# basestation_lorawan.net
KiCad netlist of a schematic drawn in EAGLE
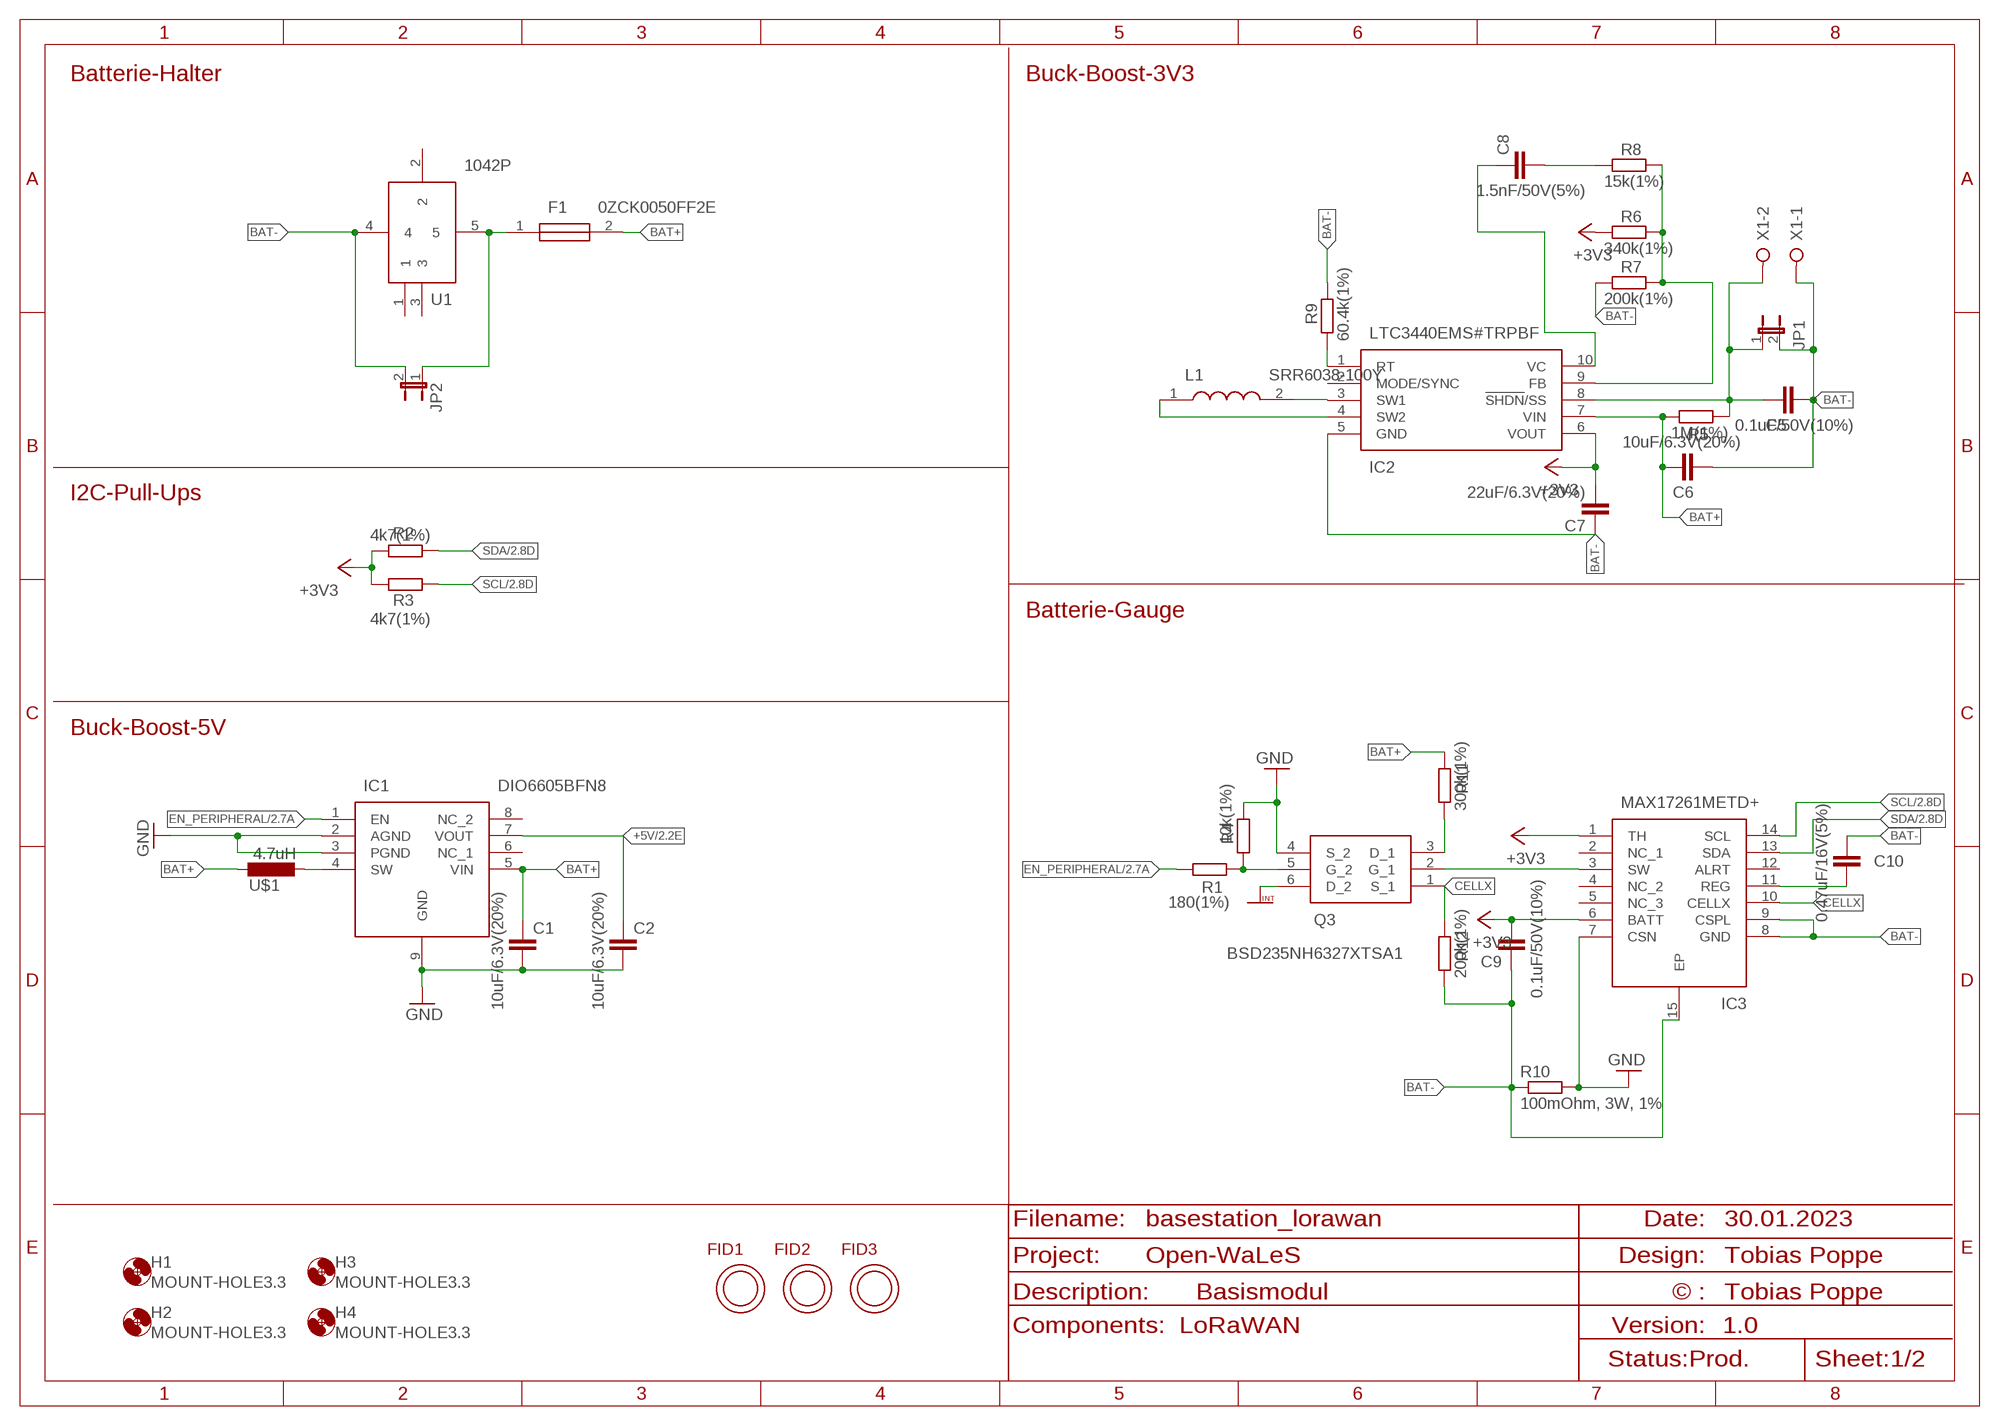
[diagram p0: schematic, sheet 1]
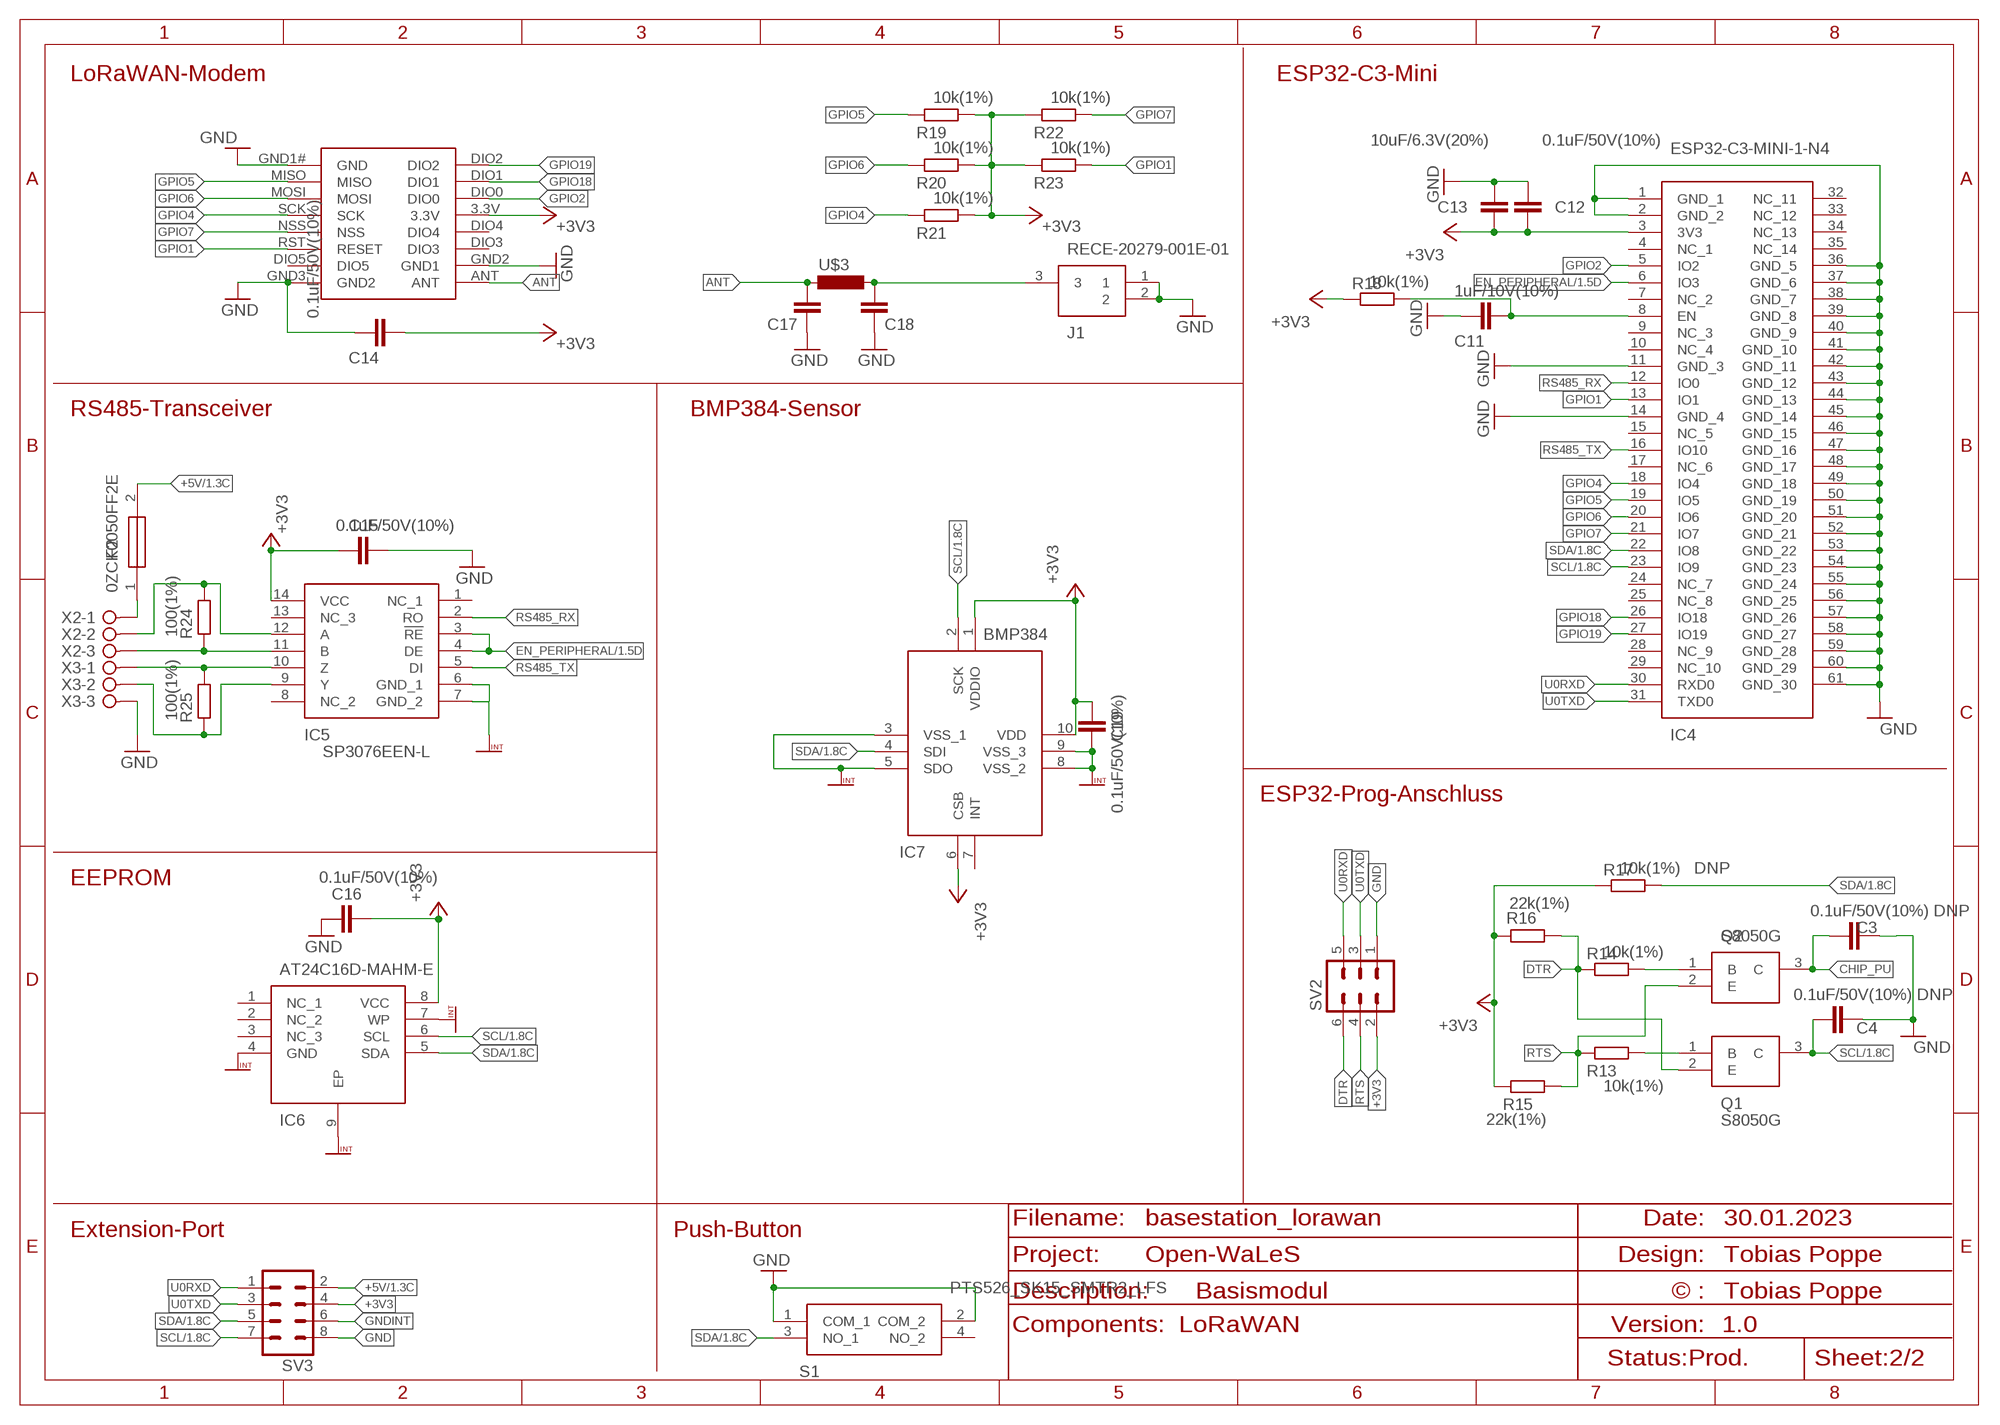
[diagram p1: schematic, sheet 2]

(export (version "E")
  (design (tool "Eeschema 10.0.6"))
  (components
    (comp (ref "C1")
      (value "10uF/6.3V(20%)")
      (footprint "eagle-import:C0805")
      (libsource (lib "eagle-import") (part "C-EUC0805"))
    )
    (comp (ref "C2")
      (value "10uF/6.3V(20%)")
      (footprint "eagle-import:C0805")
      (libsource (lib "eagle-import") (part "C-EUC0805"))
    )
    (comp (ref "C5")
      (value "0.1uF/50V(10%)")
      (footprint "eagle-import:C0805")
      (libsource (lib "eagle-import") (part "C-EUC0805"))
    )
    (comp (ref "C6")
      (value "10uF/6.3V(20%)")
      (footprint "eagle-import:C0805")
      (libsource (lib "eagle-import") (part "C-EUC0805"))
    )
    (comp (ref "C7")
      (value "22uF/6.3V(20%)")
      (footprint "eagle-import:C0805K")
      (libsource (lib "eagle-import") (part "C-EUC0805K"))
    )
    (comp (ref "C8")
      (value "1.5nF/50V(5%)")
      (footprint "eagle-import:C0805")
      (libsource (lib "eagle-import") (part "C-EUC0805"))
    )
    (comp (ref "C9")
      (value "0.1uF/50V(10%)")
      (footprint "eagle-import:C0805")
      (libsource (lib "eagle-import") (part "C-EUC0805"))
    )
    (comp (ref "C10")
      (value "0.47uF/16V(5%)")
      (footprint "eagle-import:C0805")
      (libsource (lib "eagle-import") (part "C-EUC0805"))
    )
    (comp (ref "F1")
      (value "0ZCK0050FF2E")
      (footprint "eagle-import:FUSC2214X125N")
      (libsource (lib "eagle-import") (part "0ZCK0050FF2E"))
    )
    (comp (ref "FID1")
      (value "OPEN-PNP-FIDUCIAL")
      (footprint "eagle-import:OPEN-PNP-FIDUCIAL")
      (libsource (lib "eagle-import") (part "OPEN-PNP-FIDUCIAL"))
    )
    (comp (ref "FID2")
      (value "OPEN-PNP-FIDUCIAL")
      (footprint "eagle-import:OPEN-PNP-FIDUCIAL")
      (libsource (lib "eagle-import") (part "OPEN-PNP-FIDUCIAL"))
    )
    (comp (ref "FID3")
      (value "OPEN-PNP-FIDUCIAL")
      (footprint "eagle-import:OPEN-PNP-FIDUCIAL")
      (libsource (lib "eagle-import") (part "OPEN-PNP-FIDUCIAL"))
    )
    (comp (ref "H1")
      (value "MOUNT-HOLE3.3")
      (footprint "eagle-import:3,3")
      (libsource (lib "eagle-import") (part "MOUNT-HOLE3.3"))
    )
    (comp (ref "H2")
      (value "MOUNT-HOLE3.3")
      (footprint "eagle-import:3,3")
      (libsource (lib "eagle-import") (part "MOUNT-HOLE3.3"))
    )
    (comp (ref "H3")
      (value "MOUNT-HOLE3.3")
      (footprint "eagle-import:3,3")
      (libsource (lib "eagle-import") (part "MOUNT-HOLE3.3"))
    )
    (comp (ref "H4")
      (value "MOUNT-HOLE3.3")
      (footprint "eagle-import:3,3")
      (libsource (lib "eagle-import") (part "MOUNT-HOLE3.3"))
    )
    (comp (ref "IC1")
      (value "DIO6605BFN8")
      (footprint "eagle-import:SON50P300X200X80-9N")
      (fields (field (name "MOUSER_PART_NUMBER") "453-DIO6605BFN8"))
      (libsource (lib "eagle-import") (part "DIO6605BFN8"))
    )
    (comp (ref "IC2")
      (value "LTC3440EMS#TRPBF")
      (footprint "eagle-import:SOP50P490X110-10N")
      (fields (field (name "MOUSER_PART_NUMBER") "584-LTC3440EMS#TRPBF"))
      (libsource (lib "eagle-import") (part "LTC3440EMS#TRPBF"))
    )
    (comp (ref "IC3")
      (value "MAX17261METD+")
      (footprint "eagle-import:SON40P300X300X80-15N")
      (fields (field (name "MOUSER_PART_NUMBER") "700-MAX17261METD+"))
      (libsource (lib "eagle-import") (part "MAX17261METD+"))
    )
    (comp (ref "JP1")
      (value "JP1E")
      (footprint "eagle-import:JP1")
      (libsource (lib "eagle-import") (part "JP1E"))
    )
    (comp (ref "JP2")
      (value "JP1E")
      (footprint "eagle-import:JP1")
      (libsource (lib "eagle-import") (part "JP1E"))
    )
    (comp (ref "L1")
      (value "SRR6038-100Y")
      (footprint "eagle-import:SRR6038330Y")
      (fields
        (field (name "ARROW_PART_NUMBER") "SRR6038-330Y")
        (field (name "MOUSER_PART_NUMBER") "652-SRR6038-330Y")
        (field (name "MOUSER_PART_NUMBER_1") "652-SRR6038-100Y")
      )
      (libsource (lib "eagle-import") (part "SRR6038-330Y"))
    )
    (comp (ref "Q3")
      (value "BSD235NH6327XTSA1")
      (footprint "eagle-import:SOT65P210X100-6N")
      (fields (field (name "MOUSER_PART_NUMBER") "726-BSD235NH6327XTS"))
      (libsource (lib "eagle-import") (part "BSD235NH6327XTSA1"))
    )
    (comp (ref "R1")
      (value "180(1%)")
      (footprint "eagle-import:M0805")
      (libsource (lib "eagle-import") (part "R-EU_M0805"))
    )
    (comp (ref "R2")
      (value "4k7(1%)")
      (footprint "eagle-import:M0805")
      (libsource (lib "eagle-import") (part "R-EU_M0805"))
    )
    (comp (ref "R3")
      (value "4k7(1%)")
      (footprint "eagle-import:M0805")
      (libsource (lib "eagle-import") (part "R-EU_M0805"))
    )
    (comp (ref "R4")
      (value "10k(1%)")
      (footprint "eagle-import:M0805")
      (libsource (lib "eagle-import") (part "R-EU_M0805"))
    )
    (comp (ref "R5")
      (value "1M(1%)")
      (footprint "eagle-import:M0805")
      (libsource (lib "eagle-import") (part "R-EU_M0805"))
    )
    (comp (ref "R6")
      (value "340k(1%)")
      (footprint "eagle-import:M0805")
      (libsource (lib "eagle-import") (part "R-EU_M0805"))
    )
    (comp (ref "R7")
      (value "200k(1%)")
      (footprint "eagle-import:M0805")
      (libsource (lib "eagle-import") (part "R-EU_M0805"))
    )
    (comp (ref "R8")
      (value "15k(1%)")
      (footprint "eagle-import:M0805")
      (libsource (lib "eagle-import") (part "R-EU_M0805"))
    )
    (comp (ref "R9")
      (value "60.4k(1%)")
      (footprint "eagle-import:M0805")
      (libsource (lib "eagle-import") (part "R-EU_M0805"))
    )
    (comp (ref "R10")
      (value "100mOhm, 3W, 1%")
      (footprint "eagle-import:R2512")
      (libsource (lib "eagle-import") (part "R-EU_R2512"))
    )
    (comp (ref "R11")
      (value "300k(1%)")
      (footprint "eagle-import:M0805")
      (libsource (lib "eagle-import") (part "R-EU_M0805"))
    )
    (comp (ref "R12")
      (value "200k(1%)")
      (footprint "eagle-import:M0805")
      (libsource (lib "eagle-import") (part "R-EU_M0805"))
    )
    (comp (ref "U$1")
      (value "4.7uH")
      (footprint "eagle-import:R0805")
      (libsource (lib "eagle-import") (part "L-0805"))
    )
    (comp (ref "U1")
      (value "1042P")
      (footprint "eagle-import:1042P")
      (fields (field (name "MOUSER_PART_NUMBER") "534-1042P"))
      (libsource (lib "eagle-import") (part "1042P"))
    )
    (comp (ref "X1")
      (value "W237-02P")
      (footprint "eagle-import:W237-132")
      (libsource (lib "eagle-import") (part "W237-02P"))
    )
    (comp (ref "C3")
      (value "0.1uF/50V(10%) DNP")
      (footprint "eagle-import:C0805")
      (libsource (lib "eagle-import") (part "C-EUC0805"))
    )
    (comp (ref "C4")
      (value "0.1uF/50V(10%) DNP")
      (footprint "eagle-import:C0805")
      (libsource (lib "eagle-import") (part "C-EUC0805"))
    )
    (comp (ref "C11")
      (value "1uF/10V(10%)")
      (footprint "eagle-import:C0805")
      (libsource (lib "eagle-import") (part "C-EUC0805"))
    )
    (comp (ref "C12")
      (value "0.1uF/50V(10%)")
      (footprint "eagle-import:C0805")
      (libsource (lib "eagle-import") (part "C-EUC0805"))
    )
    (comp (ref "C13")
      (value "10uF/6.3V(20%)")
      (footprint "eagle-import:C0805")
      (libsource (lib "eagle-import") (part "C-EUC0805"))
    )
    (comp (ref "C14")
      (value "0.1uF/50V(10%)")
      (footprint "eagle-import:C0805")
      (libsource (lib "eagle-import") (part "C-EUC0805"))
    )
    (comp (ref "C15")
      (value "0.1uF/50V(10%)")
      (footprint "eagle-import:C0805")
      (libsource (lib "eagle-import") (part "C-EUC0805"))
    )
    (comp (ref "C16")
      (value "0.1uF/50V(10%)")
      (footprint "eagle-import:C0805")
      (libsource (lib "eagle-import") (part "C-EUC0805"))
    )
    (comp (ref "C17")
      (value "C-EUC0805K")
      (footprint "eagle-import:C0805K")
      (libsource (lib "eagle-import") (part "C-EUC0805K"))
    )
    (comp (ref "C18")
      (value "C-EUC0805K")
      (footprint "eagle-import:C0805K")
      (libsource (lib "eagle-import") (part "C-EUC0805K"))
    )
    (comp (ref "C19")
      (value "0.1uF/50V(10%)")
      (footprint "eagle-import:C0805")
      (libsource (lib "eagle-import") (part "C-EUC0805"))
    )
    (comp (ref "F2")
      (value "0ZCK0050FF2E")
      (footprint "eagle-import:FUSC2214X125N")
      (libsource (lib "eagle-import") (part "0ZCK0050FF2E"))
    )
    (comp (ref "IC4")
      (value "ESP32-C3-MINI-1-N4")
      (footprint "eagle-import:ESP32C3MINI1N4")
      (fields (field (name "MOUSER_PART_NUMBER") "356-ESP32-C3-MINI1N4"))
      (libsource (lib "eagle-import") (part "ESP32-C3-MINI-1-N4"))
    )
    (comp (ref "IC5")
      (value "SP3076EEN-L")
      (footprint "eagle-import:SOIC127P600X175-14N")
      (fields (field (name "MOUSER_PART_NUMBER") "701-SP3076EEN-L"))
      (libsource (lib "eagle-import") (part "SP3076EEN-L"))
    )
    (comp (ref "IC6")
      (value "AT24C16D-MAHM-E")
      (footprint "eagle-import:SON50P300X200X60-9N")
      (fields (field (name "MOUSER_PART_NUMBER") "579-AT24C16D-MAHM-E"))
      (libsource (lib "eagle-import") (part "AT24C16D-MAHM-E"))
    )
    (comp (ref "IC7")
      (value "BMP384")
      (footprint "eagle-import:BMP384")
      (fields (field (name "MOUSER_PART_NUMBER") "262-BMP384"))
      (libsource (lib "eagle-import") (part "BMP384"))
    )
    (comp (ref "J1")
      (value "RECE-20279-001E-01")
      (footprint "eagle-import:RECE.20279.001E.01")
      (libsource (lib "eagle-import") (part "RECE-20279-001E-01"))
    )
    (comp (ref "Q1")
      (value "S8050G")
      (footprint "eagle-import:SOT95P240X110-3N")
      (libsource (lib "eagle-import") (part "S8050G"))
    )
    (comp (ref "Q2")
      (value "S8050G")
      (footprint "eagle-import:SOT95P240X110-3N")
      (libsource (lib "eagle-import") (part "S8050G"))
    )
    (comp (ref "R13")
      (value "10k(1%)")
      (footprint "eagle-import:M0805")
      (libsource (lib "eagle-import") (part "R-EU_M0805"))
    )
    (comp (ref "R14")
      (value "10k(1%)")
      (footprint "eagle-import:M0805")
      (libsource (lib "eagle-import") (part "R-EU_M0805"))
    )
    (comp (ref "R15")
      (value "22k(1%)")
      (footprint "eagle-import:M0805")
      (libsource (lib "eagle-import") (part "R-EU_M0805"))
    )
    (comp (ref "R16")
      (value "22k(1%)")
      (footprint "eagle-import:M0805")
      (libsource (lib "eagle-import") (part "R-EU_M0805"))
    )
    (comp (ref "R17")
      (value "10k(1%) DNP")
      (footprint "eagle-import:M0805")
      (libsource (lib "eagle-import") (part "R-EU_M0805"))
    )
    (comp (ref "R18")
      (value "10k(1%)")
      (footprint "eagle-import:M0805")
      (libsource (lib "eagle-import") (part "R-EU_M0805"))
    )
    (comp (ref "R19")
      (value "10k(1%)")
      (footprint "eagle-import:M0805")
      (libsource (lib "eagle-import") (part "R-EU_M0805"))
    )
    (comp (ref "R20")
      (value "10k(1%)")
      (footprint "eagle-import:M0805")
      (libsource (lib "eagle-import") (part "R-EU_M0805"))
    )
    (comp (ref "R21")
      (value "10k(1%)")
      (footprint "eagle-import:M0805")
      (libsource (lib "eagle-import") (part "R-EU_M0805"))
    )
    (comp (ref "R22")
      (value "10k(1%)")
      (footprint "eagle-import:M0805")
      (libsource (lib "eagle-import") (part "R-EU_M0805"))
    )
    (comp (ref "R23")
      (value "10k(1%)")
      (footprint "eagle-import:M0805")
      (libsource (lib "eagle-import") (part "R-EU_M0805"))
    )
    (comp (ref "R24")
      (value "100(1%)")
      (footprint "eagle-import:M0805")
      (libsource (lib "eagle-import") (part "R-EU_M0805"))
    )
    (comp (ref "R25")
      (value "100(1%)")
      (footprint "eagle-import:M0805")
      (libsource (lib "eagle-import") (part "R-EU_M0805"))
    )
    (comp (ref "S1")
      (value "PTS526_SK15_SMTR2_LFS")
      (footprint "eagle-import:PTS526SK15SMTR2LFS")
      (fields
        (field (name "ARROW_PART_NUMBER") "PTS526 SK15 SMTR2 LFS")
        (field (name "MOUSER_PART_NUMBER") "611-PTS526SK15SMR2L")
      )
      (libsource (lib "eagle-import") (part "PTS526_SK15_SMTR2_LFS"))
    )
    (comp (ref "SV2")
      (value "MA03-2")
      (footprint "eagle-import:MA03-2")
      (libsource (lib "eagle-import") (part "MA03-2"))
    )
    (comp (ref "SV3")
      (value "MA04-2")
      (footprint "eagle-import:MA04-2")
      (libsource (lib "eagle-import") (part "MA04-2"))
    )
    (comp (ref "U$2")
      (value "RFM95W")
      (footprint "eagle-import:RFM95W")
      (libsource (lib "eagle-import") (part "RFM95W"))
    )
    (comp (ref "U$3")
      (value "L-0805")
      (footprint "eagle-import:R0805")
      (libsource (lib "eagle-import") (part "L-0805"))
    )
    (comp (ref "X2")
      (value "W237-3E")
      (footprint "eagle-import:W237-3E")
      (libsource (lib "eagle-import") (part "W237-3E"))
    )
    (comp (ref "X3")
      (value "W237-3E")
      (footprint "eagle-import:W237-3E")
      (libsource (lib "eagle-import") (part "W237-3E"))
    )
  )
  (nets
    (net (code "1") (name "+3V3") (class "Default")
      (node (ref "C12") (pin "1") (pinfunction "1_1") (pintype "passive"))
      (node (ref "C13") (pin "2") (pinfunction "2_2") (pintype "passive"))
      (node (ref "C14") (pin "1") (pinfunction "1_1") (pintype "passive"))
      (node (ref "C15") (pin "1") (pinfunction "1_1") (pintype "passive"))
      (node (ref "C16") (pin "2") (pinfunction "2_2") (pintype "passive"))
      (node (ref "C19") (pin "1") (pinfunction "1_1") (pintype "passive"))
      (node (ref "C7") (pin "2") (pinfunction "2_2") (pintype "passive"))
      (node (ref "C9") (pin "2") (pinfunction "2_2") (pintype "passive"))
      (node (ref "IC2") (pin "6") (pinfunction "VOUT_6") (pintype "bidirectional"))
      (node (ref "IC3") (pin "1") (pinfunction "TH_1") (pintype "bidirectional"))
      (node (ref "IC3") (pin "6") (pinfunction "BATT_6") (pintype "bidirectional"))
      (node (ref "IC4") (pin "3") (pinfunction "3V3_3") (pintype "bidirectional"))
      (node (ref "IC5") (pin "14") (pinfunction "VCC_14") (pintype "bidirectional"))
      (node (ref "IC6") (pin "8") (pinfunction "VCC_8") (pintype "bidirectional"))
      (node (ref "IC7") (pin "1") (pinfunction "VDDIO_1") (pintype "bidirectional"))
      (node (ref "IC7") (pin "10") (pinfunction "VDD_10") (pintype "bidirectional"))
      (node (ref "IC7") (pin "6") (pinfunction "CSB_6") (pintype "bidirectional"))
      (node (ref "R15") (pin "2") (pinfunction "2_2") (pintype "passive"))
      (node (ref "R16") (pin "1") (pinfunction "1_1") (pintype "passive"))
      (node (ref "R17") (pin "2") (pinfunction "2_2") (pintype "passive"))
      (node (ref "R18") (pin "2") (pinfunction "2_2") (pintype "passive"))
      (node (ref "R19") (pin "1") (pinfunction "1_1") (pintype "passive"))
      (node (ref "R2") (pin "2") (pinfunction "2_2") (pintype "passive"))
      (node (ref "R20") (pin "1") (pinfunction "1_1") (pintype "passive"))
      (node (ref "R21") (pin "1") (pinfunction "1_1") (pintype "passive"))
      (node (ref "R22") (pin "2") (pinfunction "2_2") (pintype "passive"))
      (node (ref "R23") (pin "2") (pinfunction "2_2") (pintype "passive"))
      (node (ref "R3") (pin "2") (pinfunction "2_2") (pintype "passive"))
      (node (ref "R6") (pin "1") (pinfunction "1_1") (pintype "passive"))
      (node (ref "SV2") (pin "2") (pinfunction "2_2") (pintype "passive"))
      (node (ref "SV3") (pin "4") (pinfunction "4_4") (pintype "passive"))
      (node (ref "U$2") (pin "3.3V") (pinfunction "3.3V_3.3V") (pintype "bidirectional"))
    )
    (net (code "2") (name "+5V") (class "Default")
      (node (ref "C2") (pin "1") (pinfunction "1_1") (pintype "passive"))
      (node (ref "F2") (pin "2") (pinfunction "2_2") (pintype "bidirectional"))
      (node (ref "IC1") (pin "7") (pinfunction "VOUT_7") (pintype "bidirectional"))
      (node (ref "SV3") (pin "2") (pinfunction "2_2") (pintype "passive"))
    )
    (net (code "3") (name "ANT") (class "Default")
      (node (ref "C17") (pin "1") (pinfunction "1_1") (pintype "passive"))
      (node (ref "U$2") (pin "ANT") (pinfunction "ANT_ANT") (pintype "bidirectional"))
      (node (ref "U$3") (pin "1") (pinfunction "1_1") (pintype "passive"))
    )
    (net (code "4") (name "BAT+") (class "Default")
      (node (ref "C1") (pin "1") (pinfunction "1_1") (pintype "passive"))
      (node (ref "C6") (pin "2") (pinfunction "2_2") (pintype "passive"))
      (node (ref "F1") (pin "2") (pinfunction "2_2") (pintype "bidirectional"))
      (node (ref "IC1") (pin "5") (pinfunction "VIN_5") (pintype "bidirectional"))
      (node (ref "IC2") (pin "7") (pinfunction "VIN_7") (pintype "bidirectional"))
      (node (ref "R11") (pin "2") (pinfunction "2_2") (pintype "passive"))
      (node (ref "R5") (pin "1") (pinfunction "1_1") (pintype "passive"))
      (node (ref "U$1") (pin "1") (pinfunction "1_1") (pintype "passive"))
    )
    (net (code "5") (name "BAT-") (class "Default")
      (node (ref "C10") (pin "1") (pinfunction "1_1") (pintype "passive"))
      (node (ref "C5") (pin "2") (pinfunction "2_2") (pintype "passive"))
      (node (ref "C6") (pin "1") (pinfunction "1_1") (pintype "passive"))
      (node (ref "C7") (pin "1") (pinfunction "1_1") (pintype "passive"))
      (node (ref "C9") (pin "1") (pinfunction "1_1") (pintype "passive"))
      (node (ref "IC2") (pin "5") (pinfunction "GND_5") (pintype "bidirectional"))
      (node (ref "IC3") (pin "15") (pinfunction "EP_15") (pintype "bidirectional"))
      (node (ref "IC3") (pin "8") (pinfunction "GND_8") (pintype "bidirectional"))
      (node (ref "IC3") (pin "9") (pinfunction "CSPL_9") (pintype "bidirectional"))
      (node (ref "JP1") (pin "2") (pinfunction "2_2") (pintype "passive"))
      (node (ref "JP2") (pin "2") (pinfunction "2_2") (pintype "passive"))
      (node (ref "R10") (pin "1") (pinfunction "1_1") (pintype "passive"))
      (node (ref "R12") (pin "1") (pinfunction "1_1") (pintype "passive"))
      (node (ref "R7") (pin "1") (pinfunction "1_1") (pintype "passive"))
      (node (ref "R9") (pin "2") (pinfunction "2_2") (pintype "passive"))
      (node (ref "U1") (pin "4") (pinfunction "4_4") (pintype "bidirectional"))
      (node (ref "X1") (pin "1") (pinfunction "KL_1") (pintype "passive"))
    )
    (net (code "6") (name "CELLX") (class "Default")
      (node (ref "IC3") (pin "10") (pinfunction "CELLX_10") (pintype "bidirectional"))
      (node (ref "Q3") (pin "1") (pinfunction "S_1_1") (pintype "bidirectional"))
      (node (ref "R12") (pin "2") (pinfunction "2_2") (pintype "passive"))
    )
    (net (code "7") (name "CHIP_PU") (class "Default")
      (node (ref "C11") (pin "1") (pinfunction "1_1") (pintype "passive"))
      (node (ref "C3") (pin "2") (pinfunction "2_2") (pintype "passive"))
      (node (ref "IC4") (pin "8") (pinfunction "EN_8") (pintype "bidirectional"))
      (node (ref "Q2") (pin "3") (pinfunction "C_3") (pintype "bidirectional"))
      (node (ref "R18") (pin "1") (pinfunction "1_1") (pintype "passive"))
    )
    (net (code "8") (name "DTR") (class "Default")
      (node (ref "Q1") (pin "2") (pinfunction "E_2") (pintype "bidirectional"))
      (node (ref "R14") (pin "2") (pinfunction "2_2") (pintype "passive"))
      (node (ref "R16") (pin "2") (pinfunction "2_2") (pintype "passive"))
      (node (ref "SV2") (pin "6") (pinfunction "6_6") (pintype "passive"))
    )
    (net (code "9") (name "EN_PERIPHERAL") (class "Default")
      (node (ref "IC1") (pin "1") (pinfunction "EN_1") (pintype "bidirectional"))
      (node (ref "IC4") (pin "6") (pinfunction "IO3_6") (pintype "bidirectional"))
      (node (ref "IC5") (pin "3") (pinfunction "~{RE}_3") (pintype "bidirectional"))
      (node (ref "IC5") (pin "4") (pinfunction "DE_4") (pintype "bidirectional"))
      (node (ref "R1") (pin "2") (pinfunction "2_2") (pintype "passive"))
    )
    (net (code "10") (name "GND") (class "Default")
      (node (ref "C1") (pin "2") (pinfunction "2_2") (pintype "passive"))
      (node (ref "C11") (pin "2") (pinfunction "2_2") (pintype "passive"))
      (node (ref "C12") (pin "2") (pinfunction "2_2") (pintype "passive"))
      (node (ref "C13") (pin "1") (pinfunction "1_1") (pintype "passive"))
      (node (ref "C14") (pin "2") (pinfunction "2_2") (pintype "passive"))
      (node (ref "C15") (pin "2") (pinfunction "2_2") (pintype "passive"))
      (node (ref "C16") (pin "1") (pinfunction "1_1") (pintype "passive"))
      (node (ref "C17") (pin "2") (pinfunction "2_2") (pintype "passive"))
      (node (ref "C18") (pin "2") (pinfunction "2_2") (pintype "passive"))
      (node (ref "C2") (pin "2") (pinfunction "2_2") (pintype "passive"))
      (node (ref "C3") (pin "1") (pinfunction "1_1") (pintype "passive"))
      (node (ref "C4") (pin "1") (pinfunction "1_1") (pintype "passive"))
      (node (ref "IC1") (pin "2") (pinfunction "AGND_2") (pintype "bidirectional"))
      (node (ref "IC1") (pin "3") (pinfunction "PGND_3") (pintype "bidirectional"))
      (node (ref "IC1") (pin "9") (pinfunction "GND_9") (pintype "bidirectional"))
      (node (ref "IC3") (pin "7") (pinfunction "CSN_7") (pintype "bidirectional"))
      (node (ref "IC4") (pin "1") (pinfunction "GND_1_1") (pintype "bidirectional"))
      (node (ref "IC4") (pin "11") (pinfunction "GND_3_11") (pintype "bidirectional"))
      (node (ref "IC4") (pin "14") (pinfunction "GND_4_14") (pintype "bidirectional"))
      (node (ref "IC4") (pin "2") (pinfunction "GND_2_2") (pintype "bidirectional"))
      (node (ref "IC4") (pin "36") (pinfunction "GND_5_36") (pintype "bidirectional"))
      (node (ref "IC4") (pin "37") (pinfunction "GND_6_37") (pintype "bidirectional"))
      (node (ref "IC4") (pin "38") (pinfunction "GND_7_38") (pintype "bidirectional"))
      (node (ref "IC4") (pin "39") (pinfunction "GND_8_39") (pintype "bidirectional"))
      (node (ref "IC4") (pin "40") (pinfunction "GND_9_40") (pintype "bidirectional"))
      (node (ref "IC4") (pin "41") (pinfunction "GND_10_41") (pintype "bidirectional"))
      (node (ref "IC4") (pin "42") (pinfunction "GND_11_42") (pintype "bidirectional"))
      (node (ref "IC4") (pin "43") (pinfunction "GND_12_43") (pintype "bidirectional"))
      (node (ref "IC4") (pin "44") (pinfunction "GND_13_44") (pintype "bidirectional"))
      (node (ref "IC4") (pin "45") (pinfunction "GND_14_45") (pintype "bidirectional"))
      (node (ref "IC4") (pin "46") (pinfunction "GND_15_46") (pintype "bidirectional"))
      (node (ref "IC4") (pin "47") (pinfunction "GND_16_47") (pintype "bidirectional"))
      (node (ref "IC4") (pin "48") (pinfunction "GND_17_48") (pintype "bidirectional"))
      (node (ref "IC4") (pin "49") (pinfunction "GND_18_49") (pintype "bidirectional"))
      (node (ref "IC4") (pin "50") (pinfunction "GND_19_50") (pintype "bidirectional"))
      (node (ref "IC4") (pin "51") (pinfunction "GND_20_51") (pintype "bidirectional"))
      (node (ref "IC4") (pin "52") (pinfunction "GND_21_52") (pintype "bidirectional"))
      (node (ref "IC4") (pin "53") (pinfunction "GND_22_53") (pintype "bidirectional"))
      (node (ref "IC4") (pin "54") (pinfunction "GND_23_54") (pintype "bidirectional"))
      (node (ref "IC4") (pin "55") (pinfunction "GND_24_55") (pintype "bidirectional"))
      (node (ref "IC4") (pin "56") (pinfunction "GND_25_56") (pintype "bidirectional"))
      (node (ref "IC4") (pin "57") (pinfunction "GND_26_57") (pintype "bidirectional"))
      (node (ref "IC4") (pin "58") (pinfunction "GND_27_58") (pintype "bidirectional"))
      (node (ref "IC4") (pin "59") (pinfunction "GND_28_59") (pintype "bidirectional"))
      (node (ref "IC4") (pin "60") (pinfunction "GND_29_60") (pintype "bidirectional"))
      (node (ref "IC4") (pin "61") (pinfunction "GND_30_61") (pintype "bidirectional"))
      (node (ref "J1") (pin "1") (pinfunction "1_1") (pintype "bidirectional"))
      (node (ref "J1") (pin "2") (pinfunction "2_2") (pintype "bidirectional"))
      (node (ref "Q3") (pin "4") (pinfunction "S_2_4") (pintype "bidirectional"))
      (node (ref "R10") (pin "2") (pinfunction "2_2") (pintype "passive"))
      (node (ref "R4") (pin "2") (pinfunction "2_2") (pintype "passive"))
      (node (ref "S1") (pin "1") (pinfunction "COM_1_1") (pintype "bidirectional"))
      (node (ref "S1") (pin "2") (pinfunction "COM_2_2") (pintype "bidirectional"))
      (node (ref "SV2") (pin "1") (pinfunction "1_1") (pintype "passive"))
      (node (ref "SV3") (pin "8") (pinfunction "8_8") (pintype "passive"))
      (node (ref "U$2") (pin "GND1#") (pinfunction "GND_GND1#") (pintype "bidirectional"))
      (node (ref "U$2") (pin "GND2") (pinfunction "GND1_GND2") (pintype "bidirectional"))
      (node (ref "U$2") (pin "GND3") (pinfunction "GND2_GND3") (pintype "bidirectional"))
      (node (ref "X3") (pin "3") (pinfunction "KL_3") (pintype "passive"))
    )
    (net (code "11") (name "GNDINT") (class "Default")
      (node (ref "C19") (pin "2") (pinfunction "2_2") (pintype "passive"))
      (node (ref "IC5") (pin "6") (pinfunction "GND_1_6") (pintype "bidirectional"))
      (node (ref "IC5") (pin "7") (pinfunction "GND_2_7") (pintype "bidirectional"))
      (node (ref "IC6") (pin "4") (pinfunction "GND_4") (pintype "bidirectional"))
      (node (ref "IC6") (pin "7") (pinfunction "WP_7") (pintype "bidirectional"))
      (node (ref "IC6") (pin "9") (pinfunction "EP_9") (pintype "bidirectional"))
      (node (ref "IC7") (pin "3") (pinfunction "VSS_1_3") (pintype "bidirectional"))
      (node (ref "IC7") (pin "5") (pinfunction "SDO_5") (pintype "bidirectional"))
      (node (ref "IC7") (pin "8") (pinfunction "VSS_2_8") (pintype "bidirectional"))
      (node (ref "IC7") (pin "9") (pinfunction "VSS_3_9") (pintype "bidirectional"))
      (node (ref "Q3") (pin "6") (pinfunction "D_2_6") (pintype "bidirectional"))
      (node (ref "SV3") (pin "6") (pinfunction "6_6") (pintype "passive"))
    )
    (net (code "12") (name "GPIO1") (class "Default")
      (node (ref "IC4") (pin "13") (pinfunction "IO1_13") (pintype "bidirectional"))
      (node (ref "R23") (pin "1") (pinfunction "1_1") (pintype "passive"))
      (node (ref "U$2") (pin "RST") (pinfunction "RESET_RST") (pintype "bidirectional"))
    )
    (net (code "13") (name "GPIO2") (class "Default")
      (node (ref "IC4") (pin "5") (pinfunction "IO2_5") (pintype "bidirectional"))
      (node (ref "U$2") (pin "DIO0") (pinfunction "DIO0_DIO0") (pintype "bidirectional"))
    )
    (net (code "14") (name "GPIO4") (class "Default")
      (node (ref "IC4") (pin "18") (pinfunction "IO4_18") (pintype "bidirectional"))
      (node (ref "R21") (pin "2") (pinfunction "2_2") (pintype "passive"))
      (node (ref "U$2") (pin "SCK") (pinfunction "SCK_SCK") (pintype "bidirectional"))
    )
    (net (code "15") (name "GPIO5") (class "Default")
      (node (ref "IC4") (pin "19") (pinfunction "IO5_19") (pintype "bidirectional"))
      (node (ref "R19") (pin "2") (pinfunction "2_2") (pintype "passive"))
      (node (ref "U$2") (pin "MISO") (pinfunction "MISO_MISO") (pintype "bidirectional"))
    )
    (net (code "16") (name "GPIO6") (class "Default")
      (node (ref "IC4") (pin "20") (pinfunction "IO6_20") (pintype "bidirectional"))
      (node (ref "R20") (pin "2") (pinfunction "2_2") (pintype "passive"))
      (node (ref "U$2") (pin "MOSI") (pinfunction "MOSI_MOSI") (pintype "bidirectional"))
    )
    (net (code "17") (name "GPIO7") (class "Default")
      (node (ref "IC4") (pin "21") (pinfunction "IO7_21") (pintype "bidirectional"))
      (node (ref "R22") (pin "1") (pinfunction "1_1") (pintype "passive"))
      (node (ref "U$2") (pin "NSS") (pinfunction "NSS_NSS") (pintype "bidirectional"))
    )
    (net (code "18") (name "GPIO18") (class "Default")
      (node (ref "IC4") (pin "26") (pinfunction "IO18_26") (pintype "bidirectional"))
      (node (ref "U$2") (pin "DIO1") (pinfunction "DIO1_DIO1") (pintype "bidirectional"))
    )
    (net (code "19") (name "GPIO19") (class "Default")
      (node (ref "IC4") (pin "27") (pinfunction "IO19_27") (pintype "bidirectional"))
      (node (ref "U$2") (pin "DIO2") (pinfunction "DIO2_DIO2") (pintype "bidirectional"))
    )
    (net (code "20") (name "Net-(C8-Pad2)") (class "Default")
      (node (ref "C8") (pin "2") (pinfunction "2_2") (pintype "passive"))
      (node (ref "R8") (pin "1") (pinfunction "1_1") (pintype "passive"))
    )
    (net (code "21") (name "Net-(C18-Pad1)") (class "Default")
      (node (ref "C18") (pin "1") (pinfunction "1_1") (pintype "passive"))
      (node (ref "J1") (pin "3") (pinfunction "3_3") (pintype "bidirectional"))
      (node (ref "U$3") (pin "2") (pinfunction "2_2") (pintype "passive"))
    )
    (net (code "22") (name "Net-(F1-Pad1)") (class "Default")
      (node (ref "F1") (pin "1") (pinfunction "1_1") (pintype "bidirectional"))
      (node (ref "JP2") (pin "1") (pinfunction "1_1") (pintype "passive"))
      (node (ref "U1") (pin "5") (pinfunction "5_5") (pintype "bidirectional"))
    )
    (net (code "23") (name "Net-(IC1-SW)") (class "Default")
      (node (ref "IC1") (pin "4") (pinfunction "SW_4") (pintype "bidirectional"))
      (node (ref "U$1") (pin "2") (pinfunction "2_2") (pintype "passive"))
    )
    (net (code "24") (name "Net-(IC2-FB)") (class "Default")
      (node (ref "IC2") (pin "9") (pinfunction "FB_9") (pintype "bidirectional"))
      (node (ref "R6") (pin "2") (pinfunction "2_2") (pintype "passive"))
      (node (ref "R7") (pin "2") (pinfunction "2_2") (pintype "passive"))
      (node (ref "R8") (pin "2") (pinfunction "2_2") (pintype "passive"))
    )
    (net (code "25") (name "Net-(IC2-RT)") (class "Default")
      (node (ref "IC2") (pin "1") (pinfunction "RT_1") (pintype "bidirectional"))
      (node (ref "R9") (pin "1") (pinfunction "1_1") (pintype "passive"))
    )
    (net (code "26") (name "Net-(IC2-SW1)") (class "Default")
      (node (ref "IC2") (pin "3") (pinfunction "SW1_3") (pintype "bidirectional"))
      (node (ref "L1") (pin "2") (pinfunction "2_2") (pintype "bidirectional"))
    )
    (net (code "27") (name "Net-(IC2-SW2)") (class "Default")
      (node (ref "IC2") (pin "4") (pinfunction "SW2_4") (pintype "bidirectional"))
      (node (ref "L1") (pin "1") (pinfunction "1_1") (pintype "bidirectional"))
    )
    (net (code "28") (name "Net-(IC2-VC)") (class "Default")
      (node (ref "C8") (pin "1") (pinfunction "1_1") (pintype "passive"))
      (node (ref "IC2") (pin "10") (pinfunction "VC_10") (pintype "bidirectional"))
    )
    (net (code "29") (name "Net-(IC2-~{SHDN}{slash}SS)") (class "Default")
      (node (ref "C5") (pin "1") (pinfunction "1_1") (pintype "passive"))
      (node (ref "IC2") (pin "8") (pinfunction "~{SHDN}/SS_8") (pintype "bidirectional"))
      (node (ref "JP1") (pin "1") (pinfunction "1_1") (pintype "passive"))
      (node (ref "R5") (pin "2") (pinfunction "2_2") (pintype "passive"))
      (node (ref "X1") (pin "2") (pinfunction "KL_2") (pintype "passive"))
    )
    (net (code "30") (name "Net-(IC3-REG)") (class "Default")
      (node (ref "C10") (pin "2") (pinfunction "2_2") (pintype "passive"))
      (node (ref "IC3") (pin "11") (pinfunction "REG_11") (pintype "bidirectional"))
    )
    (net (code "31") (name "Net-(IC3-SW)") (class "Default")
      (node (ref "IC3") (pin "3") (pinfunction "SW_3") (pintype "bidirectional"))
      (node (ref "Q3") (pin "2") (pinfunction "G_1_2") (pintype "bidirectional"))
    )
    (net (code "32") (name "Net-(IC5-A)") (class "Default")
      (node (ref "IC5") (pin "12") (pinfunction "A_12") (pintype "bidirectional"))
      (node (ref "R24") (pin "2") (pinfunction "2_2") (pintype "passive"))
      (node (ref "X2") (pin "2") (pinfunction "KL_2") (pintype "passive"))
    )
    (net (code "33") (name "Net-(IC5-B)") (class "Default")
      (node (ref "IC5") (pin "11") (pinfunction "B_11") (pintype "bidirectional"))
      (node (ref "R24") (pin "1") (pinfunction "1_1") (pintype "passive"))
      (node (ref "X2") (pin "3") (pinfunction "KL_3") (pintype "passive"))
    )
    (net (code "34") (name "Net-(IC5-Y)") (class "Default")
      (node (ref "IC5") (pin "9") (pinfunction "Y_9") (pintype "bidirectional"))
      (node (ref "R25") (pin "1") (pinfunction "1_1") (pintype "passive"))
      (node (ref "X3") (pin "2") (pinfunction "KL_2") (pintype "passive"))
    )
    (net (code "35") (name "Net-(IC5-Z)") (class "Default")
      (node (ref "IC5") (pin "10") (pinfunction "Z_10") (pintype "bidirectional"))
      (node (ref "R25") (pin "2") (pinfunction "2_2") (pintype "passive"))
      (node (ref "X3") (pin "1") (pinfunction "KL_1") (pintype "passive"))
    )
    (net (code "36") (name "Net-(Q1-B)") (class "Default")
      (node (ref "Q1") (pin "1") (pinfunction "B_1") (pintype "bidirectional"))
      (node (ref "R13") (pin "1") (pinfunction "1_1") (pintype "passive"))
    )
    (net (code "37") (name "Net-(Q2-B)") (class "Default")
      (node (ref "Q2") (pin "1") (pinfunction "B_1") (pintype "bidirectional"))
      (node (ref "R14") (pin "1") (pinfunction "1_1") (pintype "passive"))
    )
    (net (code "38") (name "Net-(Q3-D_1)") (class "Default")
      (node (ref "Q3") (pin "3") (pinfunction "D_1_3") (pintype "bidirectional"))
      (node (ref "R11") (pin "1") (pinfunction "1_1") (pintype "passive"))
    )
    (net (code "39") (name "Net-(Q3-G_2)") (class "Default")
      (node (ref "Q3") (pin "5") (pinfunction "G_2_5") (pintype "bidirectional"))
      (node (ref "R1") (pin "1") (pinfunction "1_1") (pintype "passive"))
      (node (ref "R4") (pin "1") (pinfunction "1_1") (pintype "passive"))
    )
    (net (code "40") (name "Net-(X2A-KL)") (class "Default")
      (node (ref "F2") (pin "1") (pinfunction "1_1") (pintype "bidirectional"))
      (node (ref "X2") (pin "1") (pinfunction "KL_1") (pintype "passive"))
    )
    (net (code "41") (name "RS485_RX") (class "Default")
      (node (ref "IC4") (pin "12") (pinfunction "IO0_12") (pintype "bidirectional"))
      (node (ref "IC5") (pin "2") (pinfunction "RO_2") (pintype "bidirectional"))
    )
    (net (code "42") (name "RS485_TX") (class "Default")
      (node (ref "IC4") (pin "16") (pinfunction "IO10_16") (pintype "bidirectional"))
      (node (ref "IC5") (pin "5") (pinfunction "DI_5") (pintype "bidirectional"))
    )
    (net (code "43") (name "RTS") (class "Default")
      (node (ref "Q2") (pin "2") (pinfunction "E_2") (pintype "bidirectional"))
      (node (ref "R13") (pin "2") (pinfunction "2_2") (pintype "passive"))
      (node (ref "R15") (pin "1") (pinfunction "1_1") (pintype "passive"))
      (node (ref "SV2") (pin "4") (pinfunction "4_4") (pintype "passive"))
    )
    (net (code "44") (name "SCL") (class "Default")
      (node (ref "C4") (pin "2") (pinfunction "2_2") (pintype "passive"))
      (node (ref "IC3") (pin "14") (pinfunction "SCL_14") (pintype "bidirectional"))
      (node (ref "IC4") (pin "23") (pinfunction "IO9_23") (pintype "bidirectional"))
      (node (ref "IC6") (pin "6") (pinfunction "SCL_6") (pintype "bidirectional"))
      (node (ref "IC7") (pin "2") (pinfunction "SCK_2") (pintype "bidirectional"))
      (node (ref "Q1") (pin "3") (pinfunction "C_3") (pintype "bidirectional"))
      (node (ref "R3") (pin "1") (pinfunction "1_1") (pintype "passive"))
      (node (ref "SV3") (pin "7") (pinfunction "7_7") (pintype "passive"))
    )
    (net (code "45") (name "SDA") (class "Default")
      (node (ref "IC3") (pin "13") (pinfunction "SDA_13") (pintype "bidirectional"))
      (node (ref "IC4") (pin "22") (pinfunction "IO8_22") (pintype "bidirectional"))
      (node (ref "IC6") (pin "5") (pinfunction "SDA_5") (pintype "bidirectional"))
      (node (ref "IC7") (pin "4") (pinfunction "SDI_4") (pintype "bidirectional"))
      (node (ref "R17") (pin "1") (pinfunction "1_1") (pintype "passive"))
      (node (ref "R2") (pin "1") (pinfunction "1_1") (pintype "passive"))
      (node (ref "S1") (pin "3") (pinfunction "NO_1_3") (pintype "bidirectional"))
      (node (ref "SV3") (pin "5") (pinfunction "5_5") (pintype "passive"))
    )
    (net (code "46") (name "U0RXD") (class "Default")
      (node (ref "IC4") (pin "30") (pinfunction "RXD0_30") (pintype "bidirectional"))
      (node (ref "SV2") (pin "5") (pinfunction "5_5") (pintype "passive"))
      (node (ref "SV3") (pin "1") (pinfunction "1_1") (pintype "passive"))
    )
    (net (code "47") (name "U0TXD") (class "Default")
      (node (ref "IC4") (pin "31") (pinfunction "TXD0_31") (pintype "bidirectional"))
      (node (ref "SV2") (pin "3") (pinfunction "3_3") (pintype "passive"))
      (node (ref "SV3") (pin "3") (pinfunction "3_3") (pintype "passive"))
    )
    (net (code "48") (name "unconnected-(IC1-NC_1-Pad6)") (class "Default")
      (node (ref "IC1") (pin "6") (pinfunction "NC_1_6") (pintype "bidirectional"))
    )
    (net (code "49") (name "unconnected-(IC1-NC_2-Pad8)") (class "Default")
      (node (ref "IC1") (pin "8") (pinfunction "NC_2_8") (pintype "bidirectional"))
    )
    (net (code "50") (name "unconnected-(IC2-MODE{slash}SYNC-Pad2)") (class "Default")
      (node (ref "IC2") (pin "2") (pinfunction "MODE/SYNC_2") (pintype "bidirectional"))
    )
    (net (code "51") (name "unconnected-(IC3-ALRT-Pad12)") (class "Default")
      (node (ref "IC3") (pin "12") (pinfunction "ALRT_12") (pintype "bidirectional"))
    )
    (net (code "52") (name "unconnected-(IC3-NC_1-Pad2)") (class "Default")
      (node (ref "IC3") (pin "2") (pinfunction "NC_1_2") (pintype "bidirectional"))
    )
    (net (code "53") (name "unconnected-(IC3-NC_2-Pad4)") (class "Default")
      (node (ref "IC3") (pin "4") (pinfunction "NC_2_4") (pintype "bidirectional"))
    )
    (net (code "54") (name "unconnected-(IC3-NC_3-Pad5)") (class "Default")
      (node (ref "IC3") (pin "5") (pinfunction "NC_3_5") (pintype "bidirectional"))
    )
    (net (code "55") (name "unconnected-(IC4-NC_1-Pad4)") (class "Default")
      (node (ref "IC4") (pin "4") (pinfunction "NC_1_4") (pintype "bidirectional"))
    )
    (net (code "56") (name "unconnected-(IC4-NC_2-Pad7)") (class "Default")
      (node (ref "IC4") (pin "7") (pinfunction "NC_2_7") (pintype "bidirectional"))
    )
    (net (code "57") (name "unconnected-(IC4-NC_3-Pad9)") (class "Default")
      (node (ref "IC4") (pin "9") (pinfunction "NC_3_9") (pintype "bidirectional"))
    )
    (net (code "58") (name "unconnected-(IC4-NC_4-Pad10)") (class "Default")
      (node (ref "IC4") (pin "10") (pinfunction "NC_4_10") (pintype "bidirectional"))
    )
    (net (code "59") (name "unconnected-(IC4-NC_5-Pad15)") (class "Default")
      (node (ref "IC4") (pin "15") (pinfunction "NC_5_15") (pintype "bidirectional"))
    )
    (net (code "60") (name "unconnected-(IC4-NC_6-Pad17)") (class "Default")
      (node (ref "IC4") (pin "17") (pinfunction "NC_6_17") (pintype "bidirectional"))
    )
    (net (code "61") (name "unconnected-(IC4-NC_7-Pad24)") (class "Default")
      (node (ref "IC4") (pin "24") (pinfunction "NC_7_24") (pintype "bidirectional"))
    )
    (net (code "62") (name "unconnected-(IC4-NC_8-Pad25)") (class "Default")
      (node (ref "IC4") (pin "25") (pinfunction "NC_8_25") (pintype "bidirectional"))
    )
    (net (code "63") (name "unconnected-(IC4-NC_9-Pad28)") (class "Default")
      (node (ref "IC4") (pin "28") (pinfunction "NC_9_28") (pintype "bidirectional"))
    )
    (net (code "64") (name "unconnected-(IC4-NC_10-Pad29)") (class "Default")
      (node (ref "IC4") (pin "29") (pinfunction "NC_10_29") (pintype "bidirectional"))
    )
    (net (code "65") (name "unconnected-(IC4-NC_11-Pad32)") (class "Default")
      (node (ref "IC4") (pin "32") (pinfunction "NC_11_32") (pintype "bidirectional"))
    )
    (net (code "66") (name "unconnected-(IC4-NC_12-Pad33)") (class "Default")
      (node (ref "IC4") (pin "33") (pinfunction "NC_12_33") (pintype "bidirectional"))
    )
    (net (code "67") (name "unconnected-(IC4-NC_13-Pad34)") (class "Default")
      (node (ref "IC4") (pin "34") (pinfunction "NC_13_34") (pintype "bidirectional"))
    )
    (net (code "68") (name "unconnected-(IC4-NC_14-Pad35)") (class "Default")
      (node (ref "IC4") (pin "35") (pinfunction "NC_14_35") (pintype "bidirectional"))
    )
    (net (code "69") (name "unconnected-(IC5-NC_1-Pad1)") (class "Default")
      (node (ref "IC5") (pin "1") (pinfunction "NC_1_1") (pintype "bidirectional"))
    )
    (net (code "70") (name "unconnected-(IC5-NC_2-Pad8)") (class "Default")
      (node (ref "IC5") (pin "8") (pinfunction "NC_2_8") (pintype "bidirectional"))
    )
    (net (code "71") (name "unconnected-(IC5-NC_3-Pad13)") (class "Default")
      (node (ref "IC5") (pin "13") (pinfunction "NC_3_13") (pintype "bidirectional"))
    )
    (net (code "72") (name "unconnected-(IC6-NC_1-Pad1)") (class "Default")
      (node (ref "IC6") (pin "1") (pinfunction "NC_1_1") (pintype "bidirectional"))
    )
    (net (code "73") (name "unconnected-(IC6-NC_2-Pad2)") (class "Default")
      (node (ref "IC6") (pin "2") (pinfunction "NC_2_2") (pintype "bidirectional"))
    )
    (net (code "74") (name "unconnected-(IC6-NC_3-Pad3)") (class "Default")
      (node (ref "IC6") (pin "3") (pinfunction "NC_3_3") (pintype "bidirectional"))
    )
    (net (code "75") (name "unconnected-(IC7-INT-Pad7)") (class "Default")
      (node (ref "IC7") (pin "7") (pinfunction "INT_7") (pintype "bidirectional"))
    )
    (net (code "76") (name "unconnected-(S1-NO_2-Pad4)") (class "Default")
      (node (ref "S1") (pin "4") (pinfunction "NO_2_4") (pintype "bidirectional"))
    )
    (net (code "77") (name "unconnected-(U$2-PadDIO3)") (class "Default")
      (node (ref "U$2") (pin "DIO3") (pinfunction "DIO3_DIO3") (pintype "bidirectional"))
    )
    (net (code "78") (name "unconnected-(U$2-PadDIO4)") (class "Default")
      (node (ref "U$2") (pin "DIO4") (pinfunction "DIO4_DIO4") (pintype "bidirectional"))
    )
    (net (code "79") (name "unconnected-(U$2-PadDIO5)") (class "Default")
      (node (ref "U$2") (pin "DIO5") (pinfunction "DIO5_DIO5") (pintype "bidirectional"))
    )
    (net (code "80") (name "unconnected-(U1-Pad1)") (class "Default")
      (node (ref "U1") (pin "1") (pinfunction "1_1") (pintype "bidirectional"))
    )
    (net (code "81") (name "unconnected-(U1-Pad2)") (class "Default")
      (node (ref "U1") (pin "2") (pinfunction "2_2") (pintype "bidirectional"))
    )
    (net (code "82") (name "unconnected-(U1-Pad3)") (class "Default")
      (node (ref "U1") (pin "3") (pinfunction "3_3") (pintype "bidirectional"))
    )
  )
)
